# PFD_for_MobiFlight.net
KiCad netlist of a schematic drawn in EAGLE
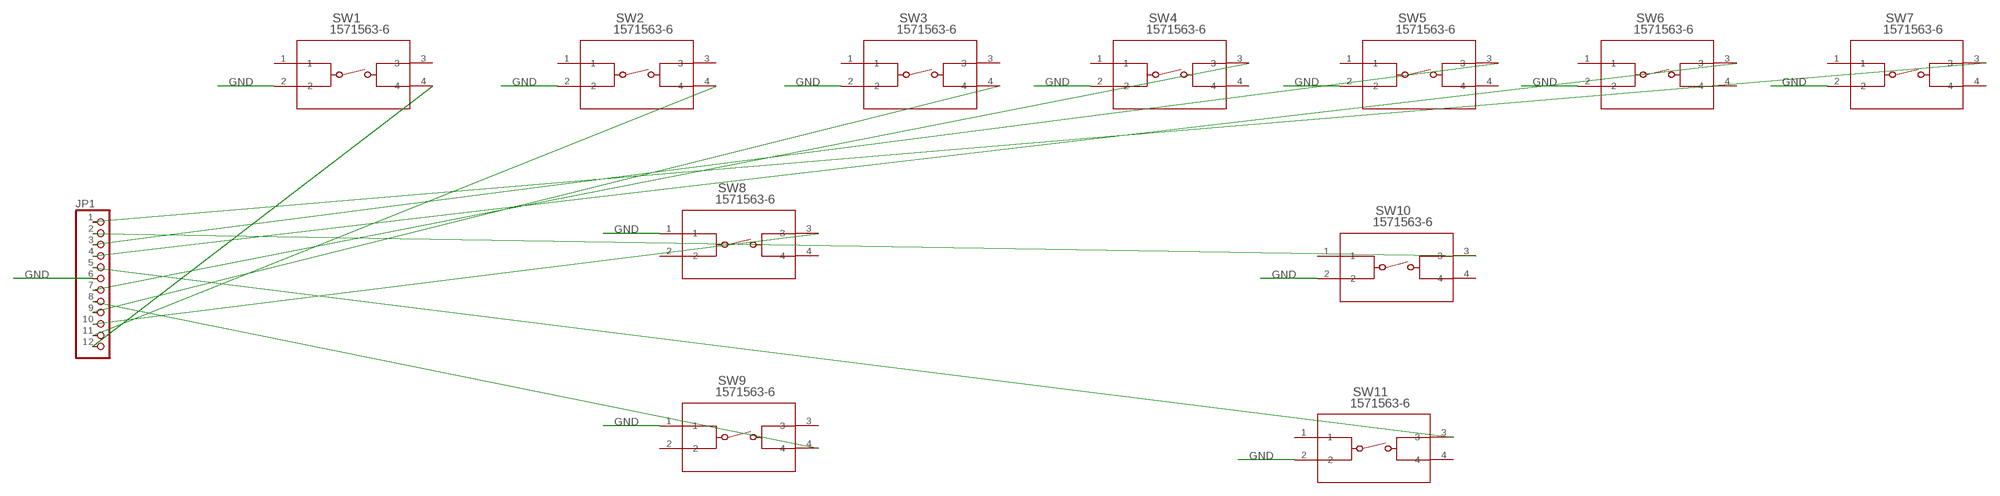
[diagram p0: schematic, sheet 1]

(export (version "E")
  (design (tool "Eeschema 10.0.6"))
  (components
    (comp (ref "JP1")
      (value "PINHD-1X12")
      (footprint "eagle-import:1X12")
      (libsource (lib "eagle-import") (part "PINHD-1X12"))
    )
    (comp (ref "SW1")
      (value "1571563-6")
      (footprint "eagle-import:SW4_1437565-E")
      (fields (field (name "COPYRIGHT") "Copyright (C) 2016 Accelerated Designs. All rights reserved"))
      (libsource (lib "eagle-import") (part "1571563-6"))
    )
    (comp (ref "SW2")
      (value "1571563-6")
      (footprint "eagle-import:SW4_1437565-E")
      (fields (field (name "COPYRIGHT") "Copyright (C) 2016 Accelerated Designs. All rights reserved"))
      (libsource (lib "eagle-import") (part "1571563-6"))
    )
    (comp (ref "SW3")
      (value "1571563-6")
      (footprint "eagle-import:SW4_1437565-E")
      (fields (field (name "COPYRIGHT") "Copyright (C) 2016 Accelerated Designs. All rights reserved"))
      (libsource (lib "eagle-import") (part "1571563-6"))
    )
    (comp (ref "SW4")
      (value "1571563-6")
      (footprint "eagle-import:SW4_1437565-E")
      (fields (field (name "COPYRIGHT") "Copyright (C) 2016 Accelerated Designs. All rights reserved"))
      (libsource (lib "eagle-import") (part "1571563-6"))
    )
    (comp (ref "SW5")
      (value "1571563-6")
      (footprint "eagle-import:SW4_1437565-E")
      (fields (field (name "COPYRIGHT") "Copyright (C) 2016 Accelerated Designs. All rights reserved"))
      (libsource (lib "eagle-import") (part "1571563-6"))
    )
    (comp (ref "SW6")
      (value "1571563-6")
      (footprint "eagle-import:SW4_1437565-E")
      (fields (field (name "COPYRIGHT") "Copyright (C) 2016 Accelerated Designs. All rights reserved"))
      (libsource (lib "eagle-import") (part "1571563-6"))
    )
    (comp (ref "SW7")
      (value "1571563-6")
      (footprint "eagle-import:SW4_1437565-E")
      (fields (field (name "COPYRIGHT") "Copyright (C) 2016 Accelerated Designs. All rights reserved"))
      (libsource (lib "eagle-import") (part "1571563-6"))
    )
    (comp (ref "SW8")
      (value "1571563-6")
      (footprint "eagle-import:SW4_1437565-E")
      (fields (field (name "COPYRIGHT") "Copyright (C) 2016 Accelerated Designs. All rights reserved"))
      (libsource (lib "eagle-import") (part "1571563-6"))
    )
    (comp (ref "SW9")
      (value "1571563-6")
      (footprint "eagle-import:SW4_1437565-E")
      (fields (field (name "COPYRIGHT") "Copyright (C) 2016 Accelerated Designs. All rights reserved"))
      (libsource (lib "eagle-import") (part "1571563-6"))
    )
    (comp (ref "SW10")
      (value "1571563-6")
      (footprint "eagle-import:SW4_1437565-E")
      (fields (field (name "COPYRIGHT") "Copyright (C) 2016 Accelerated Designs. All rights reserved"))
      (libsource (lib "eagle-import") (part "1571563-6"))
    )
    (comp (ref "SW11")
      (value "1571563-6")
      (footprint "eagle-import:SW4_1437565-E")
      (fields (field (name "COPYRIGHT") "Copyright (C) 2016 Accelerated Designs. All rights reserved"))
      (libsource (lib "eagle-import") (part "1571563-6"))
    )
  )
  (nets
    (net (code "1") (name "/GND") (class "Default")
      (node (ref "JP1") (pin "6") (pinfunction "6_6") (pintype "passive"))
      (node (ref "SW1") (pin "2") (pinfunction "2_2") (pintype "passive"))
      (node (ref "SW10") (pin "2") (pinfunction "2_2") (pintype "passive"))
      (node (ref "SW11") (pin "2") (pinfunction "2_2") (pintype "passive"))
      (node (ref "SW2") (pin "2") (pinfunction "2_2") (pintype "passive"))
      (node (ref "SW3") (pin "2") (pinfunction "2_2") (pintype "passive"))
      (node (ref "SW4") (pin "2") (pinfunction "2_2") (pintype "passive"))
      (node (ref "SW5") (pin "2") (pinfunction "2_2") (pintype "passive"))
      (node (ref "SW6") (pin "2") (pinfunction "2_2") (pintype "passive"))
      (node (ref "SW7") (pin "2") (pinfunction "2_2") (pintype "passive"))
      (node (ref "SW8") (pin "1") (pinfunction "1_1") (pintype "passive"))
      (node (ref "SW9") (pin "1") (pinfunction "1_1") (pintype "passive"))
    )
    (net (code "2") (name "Net-(JP1-Pad1)") (class "Default")
      (node (ref "JP1") (pin "1") (pinfunction "1_1") (pintype "passive"))
      (node (ref "SW7") (pin "3") (pinfunction "3_3") (pintype "passive"))
    )
    (net (code "3") (name "Net-(JP1-Pad2)") (class "Default")
      (node (ref "JP1") (pin "2") (pinfunction "2_2") (pintype "passive"))
      (node (ref "SW10") (pin "3") (pinfunction "3_3") (pintype "passive"))
    )
    (net (code "4") (name "Net-(JP1-Pad3)") (class "Default")
      (node (ref "JP1") (pin "3") (pinfunction "3_3") (pintype "passive"))
      (node (ref "SW5") (pin "3") (pinfunction "3_3") (pintype "passive"))
    )
    (net (code "5") (name "Net-(JP1-Pad4)") (class "Default")
      (node (ref "JP1") (pin "4") (pinfunction "4_4") (pintype "passive"))
      (node (ref "SW6") (pin "3") (pinfunction "3_3") (pintype "passive"))
    )
    (net (code "6") (name "Net-(JP1-Pad5)") (class "Default")
      (node (ref "JP1") (pin "5") (pinfunction "5_5") (pintype "passive"))
      (node (ref "SW11") (pin "3") (pinfunction "3_3") (pintype "passive"))
    )
    (net (code "7") (name "Net-(JP1-Pad7)") (class "Default")
      (node (ref "JP1") (pin "7") (pinfunction "7_7") (pintype "passive"))
      (node (ref "SW4") (pin "3") (pinfunction "3_3") (pintype "passive"))
    )
    (net (code "8") (name "Net-(JP1-Pad8)") (class "Default")
      (node (ref "JP1") (pin "8") (pinfunction "8_8") (pintype "passive"))
      (node (ref "SW9") (pin "4") (pinfunction "4_4") (pintype "passive"))
    )
    (net (code "9") (name "Net-(JP1-Pad9)") (class "Default")
      (node (ref "JP1") (pin "9") (pinfunction "9_9") (pintype "passive"))
      (node (ref "SW3") (pin "4") (pinfunction "4_4") (pintype "passive"))
    )
    (net (code "10") (name "Net-(JP1-Pad10)") (class "Default")
      (node (ref "JP1") (pin "10") (pinfunction "10_10") (pintype "passive"))
      (node (ref "SW8") (pin "3") (pinfunction "3_3") (pintype "passive"))
    )
    (net (code "11") (name "Net-(JP1-Pad11)") (class "Default")
      (node (ref "JP1") (pin "11") (pinfunction "11_11") (pintype "passive"))
      (node (ref "SW2") (pin "4") (pinfunction "4_4") (pintype "passive"))
    )
    (net (code "12") (name "Net-(JP1-Pad12)") (class "Default")
      (node (ref "JP1") (pin "12") (pinfunction "12_12") (pintype "passive"))
      (node (ref "SW1") (pin "4") (pinfunction "4_4") (pintype "passive"))
    )
    (net (code "13") (name "unconnected-(SW1-Pad1)") (class "Default")
      (node (ref "SW1") (pin "1") (pinfunction "1_1") (pintype "passive"))
    )
    (net (code "14") (name "unconnected-(SW1-Pad3)") (class "Default")
      (node (ref "SW1") (pin "3") (pinfunction "3_3") (pintype "passive"))
    )
    (net (code "15") (name "unconnected-(SW2-Pad1)") (class "Default")
      (node (ref "SW2") (pin "1") (pinfunction "1_1") (pintype "passive"))
    )
    (net (code "16") (name "unconnected-(SW2-Pad3)") (class "Default")
      (node (ref "SW2") (pin "3") (pinfunction "3_3") (pintype "passive"))
    )
    (net (code "17") (name "unconnected-(SW3-Pad1)") (class "Default")
      (node (ref "SW3") (pin "1") (pinfunction "1_1") (pintype "passive"))
    )
    (net (code "18") (name "unconnected-(SW3-Pad3)") (class "Default")
      (node (ref "SW3") (pin "3") (pinfunction "3_3") (pintype "passive"))
    )
    (net (code "19") (name "unconnected-(SW4-Pad1)") (class "Default")
      (node (ref "SW4") (pin "1") (pinfunction "1_1") (pintype "passive"))
    )
    (net (code "20") (name "unconnected-(SW4-Pad4)") (class "Default")
      (node (ref "SW4") (pin "4") (pinfunction "4_4") (pintype "passive"))
    )
    (net (code "21") (name "unconnected-(SW5-Pad1)") (class "Default")
      (node (ref "SW5") (pin "1") (pinfunction "1_1") (pintype "passive"))
    )
    (net (code "22") (name "unconnected-(SW5-Pad4)") (class "Default")
      (node (ref "SW5") (pin "4") (pinfunction "4_4") (pintype "passive"))
    )
    (net (code "23") (name "unconnected-(SW6-Pad1)") (class "Default")
      (node (ref "SW6") (pin "1") (pinfunction "1_1") (pintype "passive"))
    )
    (net (code "24") (name "unconnected-(SW6-Pad4)") (class "Default")
      (node (ref "SW6") (pin "4") (pinfunction "4_4") (pintype "passive"))
    )
    (net (code "25") (name "unconnected-(SW7-Pad1)") (class "Default")
      (node (ref "SW7") (pin "1") (pinfunction "1_1") (pintype "passive"))
    )
    (net (code "26") (name "unconnected-(SW7-Pad4)") (class "Default")
      (node (ref "SW7") (pin "4") (pinfunction "4_4") (pintype "passive"))
    )
    (net (code "27") (name "unconnected-(SW8-Pad2)") (class "Default")
      (node (ref "SW8") (pin "2") (pinfunction "2_2") (pintype "passive"))
    )
    (net (code "28") (name "unconnected-(SW8-Pad4)") (class "Default")
      (node (ref "SW8") (pin "4") (pinfunction "4_4") (pintype "passive"))
    )
    (net (code "29") (name "unconnected-(SW9-Pad2)") (class "Default")
      (node (ref "SW9") (pin "2") (pinfunction "2_2") (pintype "passive"))
    )
    (net (code "30") (name "unconnected-(SW9-Pad3)") (class "Default")
      (node (ref "SW9") (pin "3") (pinfunction "3_3") (pintype "passive"))
    )
    (net (code "31") (name "unconnected-(SW10-Pad1)") (class "Default")
      (node (ref "SW10") (pin "1") (pinfunction "1_1") (pintype "passive"))
    )
    (net (code "32") (name "unconnected-(SW10-Pad4)") (class "Default")
      (node (ref "SW10") (pin "4") (pinfunction "4_4") (pintype "passive"))
    )
    (net (code "33") (name "unconnected-(SW11-Pad1)") (class "Default")
      (node (ref "SW11") (pin "1") (pinfunction "1_1") (pintype "passive"))
    )
    (net (code "34") (name "unconnected-(SW11-Pad4)") (class "Default")
      (node (ref "SW11") (pin "4") (pinfunction "4_4") (pintype "passive"))
    )
  )
)
